# 3_3V_Reference.net
KiCad netlist of a schematic drawn in EAGLE
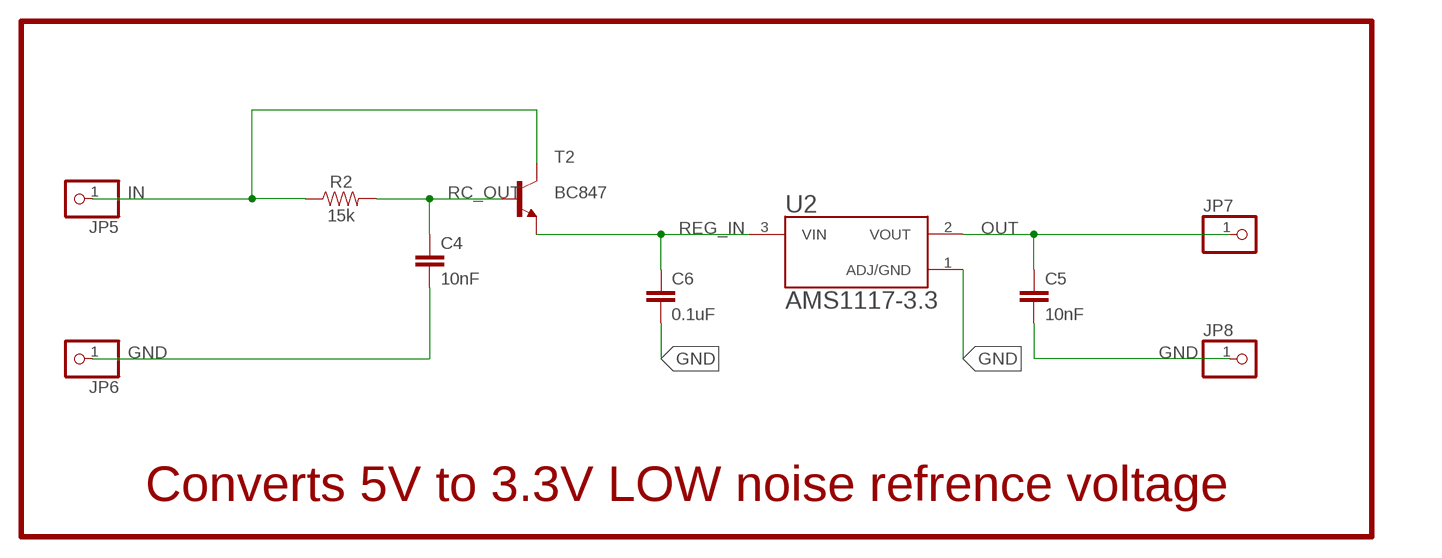
[diagram p0: schematic, sheet 1]

(export (version "E")
  (design (tool "Eeschema 10.0.6"))
  (components
    (comp (ref "C4")
      (value "10nF")
      (footprint "eagle-import:0603")
      (libsource (lib "eagle-import") (part "10NF-0603-50V-10%"))
    )
    (comp (ref "C5")
      (value "10nF")
      (footprint "eagle-import:0603")
      (libsource (lib "eagle-import") (part "10NF-0603-50V-10%"))
    )
    (comp (ref "C6")
      (value "0.1uF")
      (footprint "eagle-import:0603")
      (libsource (lib "eagle-import") (part "0.1UF-0603-25V-(+80/-20%)"))
    )
    (comp (ref "JP5")
      (value "PINHD-1X1")
      (footprint "eagle-import:1X01")
      (libsource (lib "eagle-import") (part "PINHD-1X1"))
    )
    (comp (ref "JP6")
      (value "PINHD-1X1")
      (footprint "eagle-import:1X01")
      (libsource (lib "eagle-import") (part "PINHD-1X1"))
    )
    (comp (ref "JP7")
      (value "PINHD-1X1")
      (footprint "eagle-import:1X01")
      (libsource (lib "eagle-import") (part "PINHD-1X1"))
    )
    (comp (ref "JP8")
      (value "PINHD-1X1")
      (footprint "eagle-import:1X01")
      (libsource (lib "eagle-import") (part "PINHD-1X1"))
    )
    (comp (ref "R2")
      (value "15k")
      (footprint "eagle-import:0603")
      (libsource (lib "eagle-import") (part "15KOHM-0603-1/10W-1%"))
    )
    (comp (ref "T2")
      (value "BC847")
      (footprint "eagle-import:SOT23")
      (fields (field (name "MF") "Rectron"))
      (libsource (lib "eagle-import") (part "BC847"))
    )
    (comp (ref "U2")
      (value "AMS1117-3.3")
      (footprint "eagle-import:SOT229P700X180-4N")
      (fields (field (name "MF") "Advanced Monolithic Systems"))
      (libsource (lib "eagle-import") (part "AMS1117-3.3"))
    )
  )
  (nets
    (net (code "1") (name "/IN") (class "Default")
      (node (ref "JP5") (pin "1") (pinfunction "1_1") (pintype "passive"))
      (node (ref "R2") (pin "1") (pinfunction "1_1") (pintype "passive"))
      (node (ref "T2") (pin "3") (pinfunction "C_3") (pintype "passive"))
    )
    (net (code "2") (name "/OUT") (class "Default")
      (node (ref "C5") (pin "1") (pinfunction "1_1") (pintype "passive"))
      (node (ref "JP7") (pin "1") (pinfunction "1_1") (pintype "passive"))
      (node (ref "U2") (pin "2") (pinfunction "VOUT_2") (pintype "output"))
    )
    (net (code "3") (name "/RC_OUT") (class "Default")
      (node (ref "C4") (pin "1") (pinfunction "1_1") (pintype "passive"))
      (node (ref "R2") (pin "2") (pinfunction "2_2") (pintype "passive"))
      (node (ref "T2") (pin "1") (pinfunction "B_1") (pintype "passive"))
    )
    (net (code "4") (name "/REG_IN") (class "Default")
      (node (ref "C6") (pin "1") (pinfunction "1_1") (pintype "passive"))
      (node (ref "T2") (pin "2") (pinfunction "E_2") (pintype "passive"))
      (node (ref "U2") (pin "3") (pinfunction "VIN_3") (pintype "input"))
    )
    (net (code "5") (name "GND") (class "Default")
      (node (ref "C4") (pin "2") (pinfunction "2_2") (pintype "passive"))
      (node (ref "C5") (pin "2") (pinfunction "2_2") (pintype "passive"))
      (node (ref "C6") (pin "2") (pinfunction "2_2") (pintype "passive"))
      (node (ref "JP6") (pin "1") (pinfunction "1_1") (pintype "passive"))
      (node (ref "JP8") (pin "1") (pinfunction "1_1") (pintype "passive"))
      (node (ref "U2") (pin "1") (pinfunction "ADJ/GND_1") (pintype "power_in"))
    )
  )
)
